# TriggerAndCVs_connectors.net
KiCad netlist of a schematic drawn in EAGLE
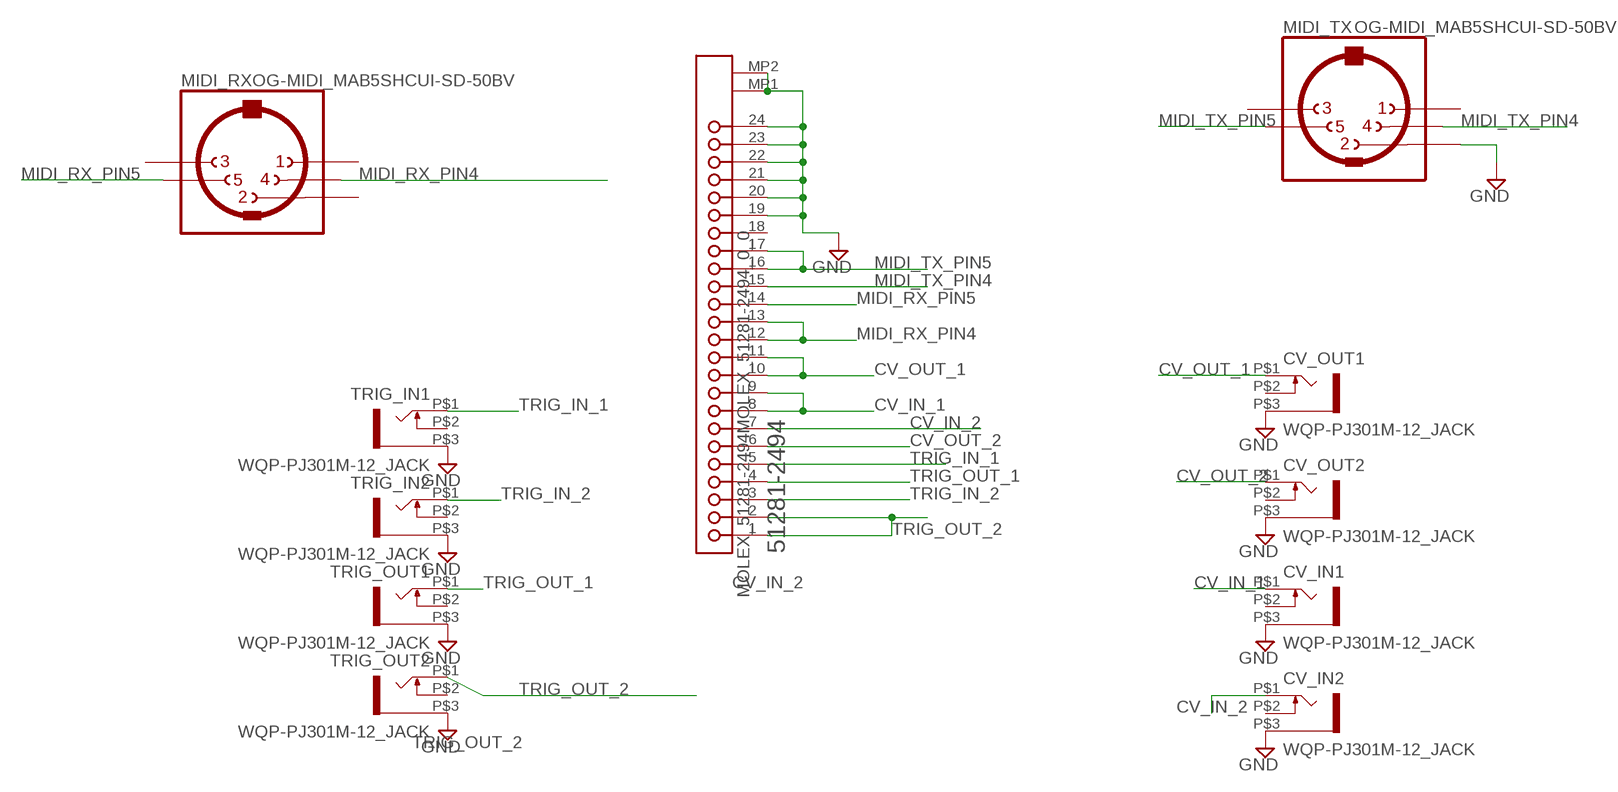
[diagram p0: schematic, sheet 1]

(export (version "E")
  (design (tool "Eeschema 10.0.6"))
  (components
    (comp (ref "CV_IN1")
      (value "WQP-PJ301M-12_JACK")
      (footprint "eagle-import:WQP-PJ301M-12_JACK")
      (libsource (lib "eagle-import") (part "WQP-PJ301M-12_JACK"))
    )
    (comp (ref "CV_IN2")
      (value "WQP-PJ301M-12_JACK")
      (footprint "eagle-import:WQP-PJ301M-12_JACK")
      (libsource (lib "eagle-import") (part "WQP-PJ301M-12_JACK"))
    )
    (comp (ref "CV_OUT1")
      (value "WQP-PJ301M-12_JACK")
      (footprint "eagle-import:WQP-PJ301M-12_JACK")
      (libsource (lib "eagle-import") (part "WQP-PJ301M-12_JACK"))
    )
    (comp (ref "CV_OUT2")
      (value "WQP-PJ301M-12_JACK")
      (footprint "eagle-import:WQP-PJ301M-12_JACK")
      (libsource (lib "eagle-import") (part "WQP-PJ301M-12_JACK"))
    )
    (comp (ref "JP4")
      (value "MOLEX_51281-2494MOLEX_51281-2494_0_0")
      (footprint "eagle-import:MOLEX_51281-2494_0")
      (fields (field (name "MF") "Molex") (field (name "MPN") "51281-2494"))
      (libsource (lib "eagle-import") (part "MOLEX_51281-2494MOLEX_51281-2494_0_0"))
    )
    (comp (ref "MIDI_RX")
      (value "OG-MIDI_MAB5SHCUI-SD-50BV")
      (footprint "eagle-import:OG-MIDI_SD-50BV")
      (libsource (lib "eagle-import") (part "OG-MIDI_MAB5SHCUI-SD-50BV"))
    )
    (comp (ref "MIDI_TX")
      (value "OG-MIDI_MAB5SHCUI-SD-50BV")
      (footprint "eagle-import:OG-MIDI_SD-50BV")
      (libsource (lib "eagle-import") (part "OG-MIDI_MAB5SHCUI-SD-50BV"))
    )
    (comp (ref "TRIG_IN1")
      (value "WQP-PJ301M-12_JACK")
      (footprint "eagle-import:WQP-PJ301M-12_JACK")
      (libsource (lib "eagle-import") (part "WQP-PJ301M-12_JACK"))
    )
    (comp (ref "TRIG_IN2")
      (value "WQP-PJ301M-12_JACK")
      (footprint "eagle-import:WQP-PJ301M-12_JACK")
      (libsource (lib "eagle-import") (part "WQP-PJ301M-12_JACK"))
    )
    (comp (ref "TRIG_OUT1")
      (value "WQP-PJ301M-12_JACK")
      (footprint "eagle-import:WQP-PJ301M-12_JACK")
      (libsource (lib "eagle-import") (part "WQP-PJ301M-12_JACK"))
    )
    (comp (ref "TRIG_OUT2")
      (value "WQP-PJ301M-12_JACK")
      (footprint "eagle-import:WQP-PJ301M-12_JACK")
      (libsource (lib "eagle-import") (part "WQP-PJ301M-12_JACK"))
    )
  )
  (nets
    (net (code "1") (name "/CV_IN_1") (class "Default")
      (node (ref "CV_IN1") (pin "P$1") (pinfunction "2_P$1") (pintype "passive"))
      (node (ref "JP4") (pin "8") (pinfunction "8_8") (pintype "passive"))
      (node (ref "JP4") (pin "9") (pinfunction "9_9") (pintype "passive"))
    )
    (net (code "2") (name "/CV_IN_2") (class "Default")
      (node (ref "CV_IN2") (pin "P$1") (pinfunction "2_P$1") (pintype "passive"))
      (node (ref "JP4") (pin "7") (pinfunction "7_7") (pintype "passive"))
    )
    (net (code "3") (name "/CV_OUT_1") (class "Default")
      (node (ref "CV_OUT1") (pin "P$1") (pinfunction "2_P$1") (pintype "passive"))
      (node (ref "JP4") (pin "10") (pinfunction "10_10") (pintype "passive"))
      (node (ref "JP4") (pin "11") (pinfunction "11_11") (pintype "passive"))
    )
    (net (code "4") (name "/CV_OUT_2") (class "Default")
      (node (ref "CV_OUT2") (pin "P$1") (pinfunction "2_P$1") (pintype "passive"))
      (node (ref "JP4") (pin "6") (pinfunction "6_6") (pintype "passive"))
    )
    (net (code "5") (name "/MIDI_RX_PIN4") (class "Default")
      (node (ref "JP4") (pin "12") (pinfunction "12_12") (pintype "passive"))
      (node (ref "JP4") (pin "13") (pinfunction "13_13") (pintype "passive"))
      (node (ref "MIDI_RX") (pin "4") (pinfunction "4_4") (pintype "passive"))
    )
    (net (code "6") (name "/MIDI_RX_PIN5") (class "Default")
      (node (ref "JP4") (pin "14") (pinfunction "14_14") (pintype "passive"))
      (node (ref "MIDI_RX") (pin "5") (pinfunction "5_5") (pintype "passive"))
    )
    (net (code "7") (name "/MIDI_TX_PIN4") (class "Default")
      (node (ref "JP4") (pin "15") (pinfunction "15_15") (pintype "passive"))
      (node (ref "MIDI_TX") (pin "4") (pinfunction "4_4") (pintype "passive"))
    )
    (net (code "8") (name "/MIDI_TX_PIN5") (class "Default")
      (node (ref "JP4") (pin "16") (pinfunction "16_16") (pintype "passive"))
      (node (ref "JP4") (pin "17") (pinfunction "17_17") (pintype "passive"))
      (node (ref "MIDI_TX") (pin "5") (pinfunction "5_5") (pintype "passive"))
    )
    (net (code "9") (name "/TRIG_IN_1") (class "Default")
      (node (ref "JP4") (pin "5") (pinfunction "5_5") (pintype "passive"))
      (node (ref "TRIG_IN1") (pin "P$1") (pinfunction "2_P$1") (pintype "passive"))
    )
    (net (code "10") (name "/TRIG_IN_2") (class "Default")
      (node (ref "JP4") (pin "3") (pinfunction "3_3") (pintype "passive"))
      (node (ref "TRIG_IN2") (pin "P$1") (pinfunction "2_P$1") (pintype "passive"))
    )
    (net (code "11") (name "/TRIG_OUT_1") (class "Default")
      (node (ref "JP4") (pin "4") (pinfunction "4_4") (pintype "passive"))
      (node (ref "TRIG_OUT1") (pin "P$1") (pinfunction "2_P$1") (pintype "passive"))
    )
    (net (code "12") (name "/TRIG_OUT_2") (class "Default")
      (node (ref "JP4") (pin "1") (pinfunction "1_1") (pintype "passive"))
      (node (ref "JP4") (pin "2") (pinfunction "2_2") (pintype "passive"))
      (node (ref "TRIG_OUT2") (pin "P$1") (pinfunction "2_P$1") (pintype "passive"))
    )
    (net (code "13") (name "GND") (class "Default")
      (node (ref "CV_IN1") (pin "P$3") (pinfunction "1_P$3") (pintype "passive"))
      (node (ref "CV_IN2") (pin "P$3") (pinfunction "1_P$3") (pintype "passive"))
      (node (ref "CV_OUT1") (pin "P$3") (pinfunction "1_P$3") (pintype "passive"))
      (node (ref "CV_OUT2") (pin "P$3") (pinfunction "1_P$3") (pintype "passive"))
      (node (ref "JP4") (pin "19") (pinfunction "19_19") (pintype "passive"))
      (node (ref "JP4") (pin "20") (pinfunction "20_20") (pintype "passive"))
      (node (ref "JP4") (pin "21") (pinfunction "21_21") (pintype "passive"))
      (node (ref "JP4") (pin "22") (pinfunction "22_22") (pintype "passive"))
      (node (ref "JP4") (pin "23") (pinfunction "23_23") (pintype "passive"))
      (node (ref "JP4") (pin "24") (pinfunction "24_24") (pintype "passive"))
      (node (ref "JP4") (pin "MP1") (pinfunction "MP1_MP1") (pintype "passive"))
      (node (ref "JP4") (pin "MP2") (pinfunction "MP2_MP2") (pintype "passive"))
      (node (ref "MIDI_TX") (pin "2") (pinfunction "2_2") (pintype "passive"))
      (node (ref "TRIG_IN1") (pin "P$3") (pinfunction "1_P$3") (pintype "passive"))
      (node (ref "TRIG_IN2") (pin "P$3") (pinfunction "1_P$3") (pintype "passive"))
      (node (ref "TRIG_OUT1") (pin "P$3") (pinfunction "1_P$3") (pintype "passive"))
      (node (ref "TRIG_OUT2") (pin "P$3") (pinfunction "1_P$3") (pintype "passive"))
    )
    (net (code "14") (name "unconnected-(CV_IN1-3-PadP$2)") (class "Default")
      (node (ref "CV_IN1") (pin "P$2") (pinfunction "3_P$2") (pintype "passive"))
    )
    (net (code "15") (name "unconnected-(CV_IN2-3-PadP$2)") (class "Default")
      (node (ref "CV_IN2") (pin "P$2") (pinfunction "3_P$2") (pintype "passive"))
    )
    (net (code "16") (name "unconnected-(CV_OUT1-3-PadP$2)") (class "Default")
      (node (ref "CV_OUT1") (pin "P$2") (pinfunction "3_P$2") (pintype "passive"))
    )
    (net (code "17") (name "unconnected-(CV_OUT2-3-PadP$2)") (class "Default")
      (node (ref "CV_OUT2") (pin "P$2") (pinfunction "3_P$2") (pintype "passive"))
    )
    (net (code "18") (name "unconnected-(JP4-Pad18)") (class "Default")
      (node (ref "JP4") (pin "18") (pinfunction "18_18") (pintype "passive"))
    )
    (net (code "19") (name "unconnected-(MIDI_RX-Pad1)") (class "Default")
      (node (ref "MIDI_RX") (pin "1") (pinfunction "1_1") (pintype "passive"))
    )
    (net (code "20") (name "unconnected-(MIDI_RX-Pad2)") (class "Default")
      (node (ref "MIDI_RX") (pin "2") (pinfunction "2_2") (pintype "passive"))
    )
    (net (code "21") (name "unconnected-(MIDI_RX-Pad3)") (class "Default")
      (node (ref "MIDI_RX") (pin "3") (pinfunction "3_3") (pintype "passive"))
    )
    (net (code "22") (name "unconnected-(MIDI_TX-Pad1)") (class "Default")
      (node (ref "MIDI_TX") (pin "1") (pinfunction "1_1") (pintype "passive"))
    )
    (net (code "23") (name "unconnected-(MIDI_TX-Pad3)") (class "Default")
      (node (ref "MIDI_TX") (pin "3") (pinfunction "3_3") (pintype "passive"))
    )
    (net (code "24") (name "unconnected-(TRIG_IN1-3-PadP$2)") (class "Default")
      (node (ref "TRIG_IN1") (pin "P$2") (pinfunction "3_P$2") (pintype "passive"))
    )
    (net (code "25") (name "unconnected-(TRIG_IN2-3-PadP$2)") (class "Default")
      (node (ref "TRIG_IN2") (pin "P$2") (pinfunction "3_P$2") (pintype "passive"))
    )
    (net (code "26") (name "unconnected-(TRIG_OUT1-3-PadP$2)") (class "Default")
      (node (ref "TRIG_OUT1") (pin "P$2") (pinfunction "3_P$2") (pintype "passive"))
    )
    (net (code "27") (name "unconnected-(TRIG_OUT2-3-PadP$2)") (class "Default")
      (node (ref "TRIG_OUT2") (pin "P$2") (pinfunction "3_P$2") (pintype "passive"))
    )
  )
)
